# Sheet1_GMAX4651_MB.net
KiCad netlist of a schematic drawn in Altium Designer
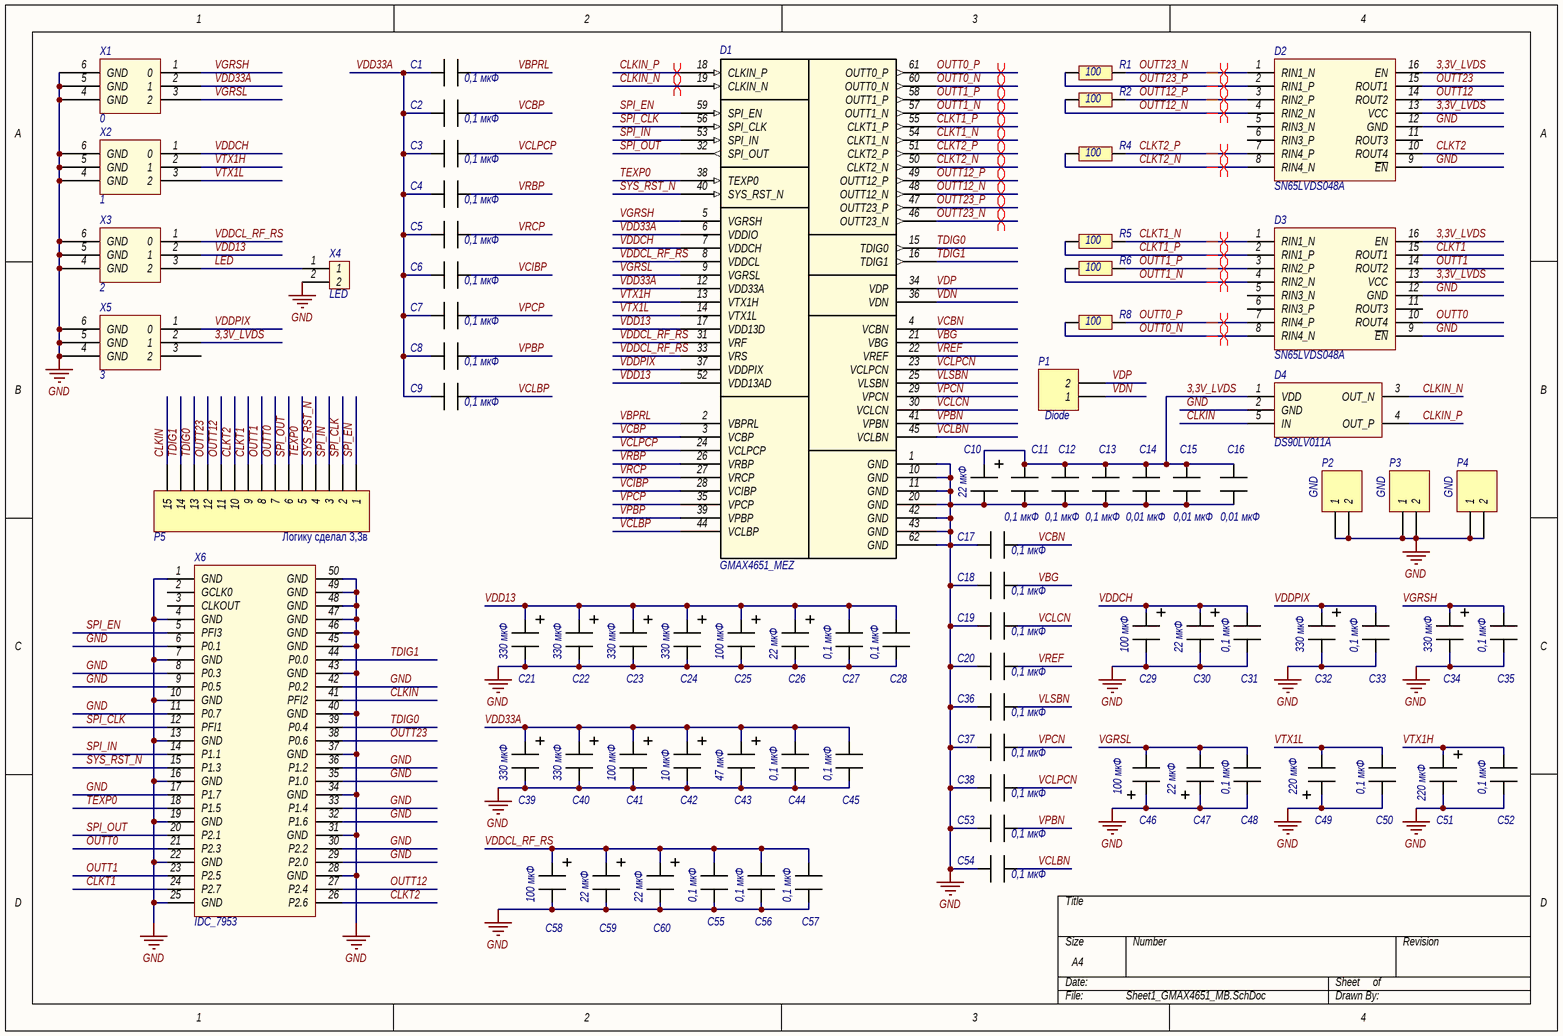
[diagram p0: Sheet1_GMAX4651_MB.SchDoc]

(export (version "E")
  (design (tool "Eeschema 10.0.6"))
  (components
    (comp (ref "C1") (value "0,1 мкФ") (footprint "CAP_SMALL") (libsource (lib "Schlib") (part "CAP_SMALL")))
    (comp (ref "C2") (value "0,1 мкФ") (footprint "CAP_SMALL") (libsource (lib "Schlib") (part "CAP_SMALL")))
    (comp (ref "C3") (value "0,1 мкФ") (footprint "CAP_SMALL") (libsource (lib "Schlib") (part "CAP_SMALL")))
    (comp (ref "C4") (value "0,1 мкФ") (footprint "CAP_SMALL") (libsource (lib "Schlib") (part "CAP_SMALL")))
    (comp (ref "C5") (value "0,1 мкФ") (footprint "CAP_SMALL") (libsource (lib "Schlib") (part "CAP_SMALL")))
    (comp (ref "C6") (value "0,1 мкФ") (footprint "CAP_SMALL") (libsource (lib "Schlib") (part "CAP_SMALL")))
    (comp (ref "C7") (value "0,1 мкФ") (footprint "CAP_SMALL") (libsource (lib "Schlib") (part "CAP_SMALL")))
    (comp (ref "C8") (value "0,1 мкФ") (footprint "CAP_SMALL") (libsource (lib "Schlib") (part "CAP_SMALL")))
    (comp (ref "C9") (value "0,1 мкФ") (footprint "CAP_SMALL") (libsource (lib "Schlib") (part "CAP_SMALL")))
    (comp (ref "C10")
      (value "22 мкФ")
      (footprint "Cap_0511_electrolitic")
      (libsource (lib "Schlib") (part "Cap_electrolotoc_0511"))
    )
    (comp (ref "C11") (value "0,1 мкФ") (footprint "CAP_SMALL") (libsource (lib "Schlib") (part "CAP_SMALL")))
    (comp (ref "C12") (value "0,1 мкФ") (footprint "CAP_SMALL") (libsource (lib "Schlib") (part "CAP_SMALL")))
    (comp (ref "C13") (value "0,1 мкФ") (footprint "CAP_SMALL") (libsource (lib "Schlib") (part "CAP_SMALL")))
    (comp (ref "C14")
      (value "0,01 мкФ")
      (footprint "CAP_SMALL")
      (libsource (lib "Schlib") (part "CAP_SMALL"))
    )
    (comp (ref "C15")
      (value "0,01 мкФ")
      (footprint "CAP_SMALL")
      (libsource (lib "Schlib") (part "CAP_SMALL"))
    )
    (comp (ref "C16")
      (value "0,01 мкФ")
      (footprint "CAP_SMALL")
      (libsource (lib "Schlib") (part "CAP_SMALL"))
    )
    (comp (ref "C17") (value "0,1 мкФ") (footprint "CAP_SMALL") (libsource (lib "Schlib") (part "CAP_SMALL")))
    (comp (ref "C18") (value "0,1 мкФ") (footprint "CAP_SMALL") (libsource (lib "Schlib") (part "CAP_SMALL")))
    (comp (ref "C19") (value "0,1 мкФ") (footprint "CAP_SMALL") (libsource (lib "Schlib") (part "CAP_SMALL")))
    (comp (ref "C20") (value "0,1 мкФ") (footprint "CAP_SMALL") (libsource (lib "Schlib") (part "CAP_SMALL")))
    (comp (ref "C21")
      (value "330 мкФ")
      (footprint "Cap_1013_electrolitic")
      (libsource (lib "Schlib") (part "Cap_electrolotoc_1013"))
    )
    (comp (ref "C22")
      (value "330 мкФ")
      (footprint "Cap_1013_electrolitic")
      (libsource (lib "Schlib") (part "Cap_electrolotoc_1013"))
    )
    (comp (ref "C23")
      (value "330 мкФ")
      (footprint "Cap_1013_electrolitic")
      (libsource (lib "Schlib") (part "Cap_electrolotoc_1013"))
    )
    (comp (ref "C24")
      (value "330 мкФ")
      (footprint "Cap_1013_electrolitic")
      (libsource (lib "Schlib") (part "Cap_electrolotoc_1013"))
    )
    (comp (ref "C25")
      (value "100 мкФ")
      (footprint "Cap_0612_electrolitic")
      (libsource (lib "Schlib") (part "Cap_electrolotoc_0612"))
    )
    (comp (ref "C26")
      (value "22 мкФ")
      (footprint "Cap_0511_electrolitic")
      (libsource (lib "Schlib") (part "Cap_electrolotoc_0511"))
    )
    (comp (ref "C27") (value "0,1 мкФ") (footprint "CAP_SMALL") (libsource (lib "Schlib") (part "CAP_SMALL")))
    (comp (ref "C28") (value "0,1 мкФ") (footprint "CAP_SMALL") (libsource (lib "Schlib") (part "CAP_SMALL")))
    (comp (ref "C29")
      (value "100 мкФ")
      (footprint "Cap_0612_electrolitic")
      (libsource (lib "Schlib") (part "Cap_electrolotoc_0612"))
    )
    (comp (ref "C30")
      (value "22 мкФ")
      (footprint "Cap_0511_electrolitic")
      (libsource (lib "Schlib") (part "Cap_electrolotoc_0511"))
    )
    (comp (ref "C31") (value "0,1 мкФ") (footprint "CAP_SMALL") (libsource (lib "Schlib") (part "CAP_SMALL")))
    (comp (ref "C32")
      (value "330 мкФ")
      (footprint "Cap_1013_electrolitic")
      (libsource (lib "Schlib") (part "Cap_electrolotoc_1013"))
    )
    (comp (ref "C33") (value "0,1 мкФ") (footprint "CAP_SMALL") (libsource (lib "Schlib") (part "CAP_SMALL")))
    (comp (ref "C34")
      (value "330 мкФ")
      (footprint "Cap_1013_electrolitic")
      (libsource (lib "Schlib") (part "Cap_electrolotoc_1013"))
    )
    (comp (ref "C35") (value "0,1 мкФ") (footprint "CAP_SMALL") (libsource (lib "Schlib") (part "CAP_SMALL")))
    (comp (ref "C36") (value "0,1 мкФ") (footprint "CAP_SMALL") (libsource (lib "Schlib") (part "CAP_SMALL")))
    (comp (ref "C37") (value "0,1 мкФ") (footprint "CAP_SMALL") (libsource (lib "Schlib") (part "CAP_SMALL")))
    (comp (ref "C38") (value "0,1 мкФ") (footprint "CAP_SMALL") (libsource (lib "Schlib") (part "CAP_SMALL")))
    (comp (ref "C39")
      (value "330 мкФ")
      (footprint "Cap_1013_electrolitic")
      (libsource (lib "Schlib") (part "Cap_electrolotoc_1013"))
    )
    (comp (ref "C40")
      (value "330 мкФ")
      (footprint "Cap_1013_electrolitic")
      (libsource (lib "Schlib") (part "Cap_electrolotoc_1013"))
    )
    (comp (ref "C41")
      (value "100 мкФ")
      (footprint "Cap_0612_electrolitic")
      (libsource (lib "Schlib") (part "Cap_electrolotoc_0612"))
    )
    (comp (ref "C42")
      (value "10 мкФ")
      (footprint "Cap_0511_electrolitic")
      (libsource (lib "Schlib") (part "Cap_electrolotoc_0511"))
    )
    (comp (ref "C43")
      (value "47 мкФ")
      (footprint "Cap_0612_electrolitic")
      (libsource (lib "Schlib") (part "Cap_electrolotoc_0612"))
    )
    (comp (ref "C44") (value "0,1 мкФ") (footprint "CAP_SMALL") (libsource (lib "Schlib") (part "CAP_SMALL")))
    (comp (ref "C45") (value "0,1 мкФ") (footprint "CAP_SMALL") (libsource (lib "Schlib") (part "CAP_SMALL")))
    (comp (ref "C46")
      (value "100 мкФ")
      (footprint "Cap_0612_electrolitic")
      (libsource (lib "Schlib") (part "Cap_electrolotoc_0612"))
    )
    (comp (ref "C47")
      (value "22 мкФ")
      (footprint "Cap_0511_electrolitic")
      (libsource (lib "Schlib") (part "Cap_electrolotoc_0511"))
    )
    (comp (ref "C48") (value "0,1 мкФ") (footprint "CAP_SMALL") (libsource (lib "Schlib") (part "CAP_SMALL")))
    (comp (ref "C49")
      (value "220 мкФ")
      (footprint "Cap_1013_electrolitic")
      (libsource (lib "Schlib") (part "Cap_electrolotoc_1013"))
    )
    (comp (ref "C50") (value "0,1 мкФ") (footprint "CAP_SMALL") (libsource (lib "Schlib") (part "CAP_SMALL")))
    (comp (ref "C51")
      (value "220 мкФ")
      (footprint "Cap_1013_electrolitic")
      (libsource (lib "Schlib") (part "Cap_electrolotoc_1013"))
    )
    (comp (ref "C52") (value "0,1 мкФ") (footprint "CAP_SMALL") (libsource (lib "Schlib") (part "CAP_SMALL")))
    (comp (ref "C53") (value "0,1 мкФ") (footprint "CAP_SMALL") (libsource (lib "Schlib") (part "CAP_SMALL")))
    (comp (ref "C54") (value "0,1 мкФ") (footprint "CAP_SMALL") (libsource (lib "Schlib") (part "CAP_SMALL")))
    (comp (ref "C55") (value "0,1 мкФ") (footprint "CAP_SMALL") (libsource (lib "Schlib") (part "CAP_SMALL")))
    (comp (ref "C56") (value "0,1 мкФ") (footprint "CAP_SMALL") (libsource (lib "Schlib") (part "CAP_SMALL")))
    (comp (ref "C57") (value "0,1 мкФ") (footprint "CAP_SMALL") (libsource (lib "Schlib") (part "CAP_SMALL")))
    (comp (ref "C58")
      (value "100 мкФ")
      (footprint "Cap_0612_electrolitic")
      (libsource (lib "Schlib") (part "Cap_electrolotoc_0612"))
    )
    (comp (ref "C59")
      (value "22 мкФ")
      (footprint "Cap_0511_electrolitic")
      (libsource (lib "Schlib") (part "Cap_electrolotoc_0511"))
    )
    (comp (ref "C60")
      (value "22 мкФ")
      (footprint "Cap_0511_electrolitic")
      (libsource (lib "Schlib") (part "Cap_electrolotoc_0511"))
    )
    (comp (ref "D1")
      (value "GMAX4651_MEZ")
      (footprint "GMAX4651_MEZ")
      (libsource (lib "Schlib") (part "GMAX4651_MEZ"))
    )
    (comp (ref "D2")
      (value "SN65LVDS048A")
      (footprint "SN65LVDS048A (4LVDS)")
      (libsource (lib "Schlib") (part "SN65LVDS048A (4LVDS)"))
    )
    (comp (ref "D3")
      (value "SN65LVDS048A")
      (footprint "SN65LVDS048A (4LVDS)")
      (libsource (lib "Schlib") (part "SN65LVDS048A (4LVDS)"))
    )
    (comp (ref "D4")
      (value "DS90LV011A")
      (footprint "DS90LV011A")
      (description "LVDS Driver 1 ch")
      (libsource (lib "Schlib") (part "DS90LV011A"))
    )
    (comp (ref "P1")
      (value "Diode")
      (footprint "HDR1X2")
      (description "Header, 2-Pin")
      (fields (field (name "PUBLISHER") "Altium Limited"))
      (libsource (lib "Miscellaneous Connectors") (part "Header 2"))
    )
    (comp (ref "P2")
      (value "GND")
      (footprint "HDR1X2")
      (description "Header, 2-Pin")
      (fields (field (name "PUBLISHER") "Altium Limited"))
      (libsource (lib "") (part "Header 2_1"))
    )
    (comp (ref "P3")
      (value "GND")
      (footprint "HDR1X2")
      (description "Header, 2-Pin")
      (fields (field (name "PUBLISHER") "Altium Limited"))
      (libsource (lib "") (part "Header 2_1"))
    )
    (comp (ref "P4")
      (value "GND")
      (footprint "HDR1X2")
      (description "Header, 2-Pin")
      (fields (field (name "PUBLISHER") "Altium Limited"))
      (libsource (lib "") (part "Header 2_1"))
    )
    (comp (ref "P5")
      (value "Header 15")
      (footprint "HDR1X15")
      (description "Header, 15-Pin")
      (fields (field (name "PUBLISHER") "Altium Limited"))
      (libsource (lib "Miscellaneous Connectors") (part "Header 15"))
    )
    (comp (ref "R1") (value "100") (footprint "RES") (libsource (lib "Schlib") (part "RES")))
    (comp (ref "R2") (value "100") (footprint "RES") (libsource (lib "Schlib") (part "RES")))
    (comp (ref "R4") (value "100") (footprint "RES") (libsource (lib "Schlib") (part "RES")))
    (comp (ref "R5") (value "100") (footprint "RES") (libsource (lib "Schlib") (part "RES")))
    (comp (ref "R6") (value "100") (footprint "RES") (libsource (lib "Schlib") (part "RES")))
    (comp (ref "R8") (value "100") (footprint "RES") (libsource (lib "Schlib") (part "RES")))
    (comp (ref "X1") (value "0") (footprint "POWER") (libsource (lib "Schlib") (part "POWER")))
    (comp (ref "X2") (value "1") (footprint "POWER") (libsource (lib "Schlib") (part "POWER")))
    (comp (ref "X3") (value "2") (footprint "POWER") (libsource (lib "Schlib") (part "POWER")))
    (comp (ref "X4") (value "LED") (footprint "KLEMMNIK_2") (libsource (lib "Schlib") (part "KLEMMNIK_2")))
    (comp (ref "X5") (value "3") (footprint "POWER") (libsource (lib "Schlib") (part "POWER")))
    (comp (ref "X6") (value "IDC_7953") (footprint "IDC_7953") (libsource (lib "VPL") (part "IDC_7953")))
  )
  (nets
    (net (code "1") (name "/3,3V_LVDS") (class "Default")
      (node (ref "C10") (pin "1") (pinfunction "1_1") (pintype "passive"))
      (node (ref "C11") (pin "2") (pinfunction "2_2") (pintype "passive"))
      (node (ref "C12") (pin "2") (pinfunction "2_2") (pintype "passive"))
      (node (ref "C13") (pin "2") (pinfunction "2_2") (pintype "passive"))
      (node (ref "C14") (pin "2") (pinfunction "2_2") (pintype "passive"))
      (node (ref "C15") (pin "2") (pinfunction "2_2") (pintype "passive"))
      (node (ref "C16") (pin "2") (pinfunction "2_2") (pintype "passive"))
      (node (ref "D2") (pin "13") (pinfunction "VCC_13") (pintype "passive"))
      (node (ref "D2") (pin "16") (pinfunction "EN_16") (pintype "passive"))
      (node (ref "D3") (pin "13") (pinfunction "VCC_13") (pintype "passive"))
      (node (ref "D3") (pin "16") (pinfunction "EN_16") (pintype "passive"))
      (node (ref "D4") (pin "1") (pinfunction "VDD_1") (pintype "passive"))
      (node (ref "X5") (pin "2") (pinfunction "1_2") (pintype "passive"))
    )
    (net (code "2") (name "/CLKIN") (class "Default")
      (node (ref "D4") (pin "5") (pinfunction "IN_5") (pintype "passive"))
      (node (ref "P5") (pin "15") (pinfunction "15_15") (pintype "passive"))
      (node (ref "X6") (pin "41") (pinfunction "PFI2_41") (pintype "passive"))
    )
    (net (code "3") (name "/CLKIN_N") (class "Default")
      (node (ref "D1") (pin "19") (pinfunction "CLKIN_N_19") (pintype "input"))
      (node (ref "D4") (pin "3") (pinfunction "OUT_N_3") (pintype "passive"))
    )
    (net (code "4") (name "/CLKIN_P") (class "Default")
      (node (ref "D1") (pin "18") (pinfunction "CLKIN_P_18") (pintype "input"))
      (node (ref "D4") (pin "4") (pinfunction "OUT_P_4") (pintype "passive"))
    )
    (net (code "5") (name "/CLKT1") (class "Default")
      (node (ref "D3") (pin "15") (pinfunction "ROUT1_15") (pintype "passive"))
      (node (ref "P5") (pin "9") (pinfunction "9_9") (pintype "passive"))
      (node (ref "X6") (pin "24") (pinfunction "P2.7_24") (pintype "passive"))
    )
    (net (code "6") (name "/CLKT1_N") (class "Default")
      (node (ref "D1") (pin "54") (pinfunction "CLKT1_N_54") (pintype "output"))
      (node (ref "D3") (pin "1") (pinfunction "RIN1_N_1") (pintype "passive"))
      (node (ref "R5") (pin "1") (pinfunction "1_1") (pintype "passive"))
    )
    (net (code "7") (name "/CLKT1_P") (class "Default")
      (node (ref "D1") (pin "55") (pinfunction "CLKT1_P_55") (pintype "output"))
      (node (ref "D3") (pin "2") (pinfunction "RIN1_P_2") (pintype "passive"))
      (node (ref "R5") (pin "2") (pinfunction "2_2") (pintype "passive"))
    )
    (net (code "8") (name "/CLKT2") (class "Default")
      (node (ref "D2") (pin "10") (pinfunction "ROUT4_10") (pintype "passive"))
      (node (ref "P5") (pin "10") (pinfunction "10_10") (pintype "passive"))
      (node (ref "X6") (pin "26") (pinfunction "P2.6_26") (pintype "passive"))
    )
    (net (code "9") (name "/CLKT2_N") (class "Default")
      (node (ref "D1") (pin "50") (pinfunction "CLKT2_N_50") (pintype "output"))
      (node (ref "D2") (pin "8") (pinfunction "RIN4_N_8") (pintype "passive"))
      (node (ref "R4") (pin "2") (pinfunction "2_2") (pintype "passive"))
    )
    (net (code "10") (name "/CLKT2_P") (class "Default")
      (node (ref "D1") (pin "51") (pinfunction "CLKT2_P_51") (pintype "output"))
      (node (ref "D2") (pin "7") (pinfunction "RIN4_P_7") (pintype "passive"))
      (node (ref "R4") (pin "1") (pinfunction "1_1") (pintype "passive"))
    )
    (net (code "11") (name "/LED") (class "Default")
      (node (ref "X3") (pin "3") (pinfunction "2_3") (pintype "passive"))
      (node (ref "X4") (pin "1") (pinfunction "1_1") (pintype "passive"))
    )
    (net (code "12") (name "/OUTT0") (class "Default")
      (node (ref "D3") (pin "10") (pinfunction "ROUT4_10") (pintype "passive"))
      (node (ref "P5") (pin "7") (pinfunction "7_7") (pintype "passive"))
      (node (ref "X6") (pin "21") (pinfunction "P2.3_21") (pintype "passive"))
    )
    (net (code "13") (name "/OUTT0_N") (class "Default")
      (node (ref "D1") (pin "60") (pinfunction "OUTT0_N_60") (pintype "output"))
      (node (ref "D3") (pin "8") (pinfunction "RIN4_N_8") (pintype "passive"))
      (node (ref "R8") (pin "2") (pinfunction "2_2") (pintype "passive"))
    )
    (net (code "14") (name "/OUTT0_P") (class "Default")
      (node (ref "D1") (pin "61") (pinfunction "OUTT0_P_61") (pintype "output"))
      (node (ref "D3") (pin "7") (pinfunction "RIN4_P_7") (pintype "passive"))
      (node (ref "R8") (pin "1") (pinfunction "1_1") (pintype "passive"))
    )
    (net (code "15") (name "/OUTT1") (class "Default")
      (node (ref "D3") (pin "14") (pinfunction "ROUT2_14") (pintype "passive"))
      (node (ref "P5") (pin "8") (pinfunction "8_8") (pintype "passive"))
      (node (ref "X6") (pin "23") (pinfunction "P2.5_23") (pintype "passive"))
    )
    (net (code "16") (name "/OUTT1_N") (class "Default")
      (node (ref "D1") (pin "57") (pinfunction "OUTT1_N_57") (pintype "output"))
      (node (ref "D3") (pin "4") (pinfunction "RIN2_N_4") (pintype "passive"))
      (node (ref "R6") (pin "2") (pinfunction "2_2") (pintype "passive"))
    )
    (net (code "17") (name "/OUTT1_P") (class "Default")
      (node (ref "D1") (pin "58") (pinfunction "OUTT1_P_58") (pintype "output"))
      (node (ref "D3") (pin "3") (pinfunction "RIN2_P_3") (pintype "passive"))
      (node (ref "R6") (pin "1") (pinfunction "1_1") (pintype "passive"))
    )
    (net (code "18") (name "/OUTT12") (class "Default")
      (node (ref "D2") (pin "14") (pinfunction "ROUT2_14") (pintype "passive"))
      (node (ref "P5") (pin "11") (pinfunction "11_11") (pintype "passive"))
      (node (ref "X6") (pin "27") (pinfunction "P2.4_27") (pintype "passive"))
    )
    (net (code "19") (name "/OUTT12_N") (class "Default")
      (node (ref "D1") (pin "48") (pinfunction "OUTT12_N_48") (pintype "output"))
      (node (ref "D2") (pin "4") (pinfunction "RIN2_N_4") (pintype "passive"))
      (node (ref "R2") (pin "2") (pinfunction "2_2") (pintype "passive"))
    )
    (net (code "20") (name "/OUTT12_P") (class "Default")
      (node (ref "D1") (pin "49") (pinfunction "OUTT12_P_49") (pintype "output"))
      (node (ref "D2") (pin "3") (pinfunction "RIN2_P_3") (pintype "passive"))
      (node (ref "R2") (pin "1") (pinfunction "1_1") (pintype "passive"))
    )
    (net (code "21") (name "/OUTT23") (class "Default")
      (node (ref "D2") (pin "15") (pinfunction "ROUT1_15") (pintype "passive"))
      (node (ref "P5") (pin "12") (pinfunction "12_12") (pintype "passive"))
      (node (ref "X6") (pin "38") (pinfunction "P0.6_38") (pintype "passive"))
    )
    (net (code "22") (name "/OUTT23_N") (class "Default")
      (node (ref "D1") (pin "46") (pinfunction "OUTT23_N_46") (pintype "output"))
      (node (ref "D2") (pin "1") (pinfunction "RIN1_N_1") (pintype "passive"))
      (node (ref "R1") (pin "1") (pinfunction "1_1") (pintype "passive"))
    )
    (net (code "23") (name "/OUTT23_P") (class "Default")
      (node (ref "D1") (pin "47") (pinfunction "OUTT23_P_47") (pintype "output"))
      (node (ref "D2") (pin "2") (pinfunction "RIN1_P_2") (pintype "passive"))
      (node (ref "R1") (pin "2") (pinfunction "2_2") (pintype "passive"))
    )
    (net (code "24") (name "/SPI_CLK") (class "Default")
      (node (ref "D1") (pin "56") (pinfunction "SPI_CLK_56") (pintype "input"))
      (node (ref "P5") (pin "2") (pinfunction "2_2") (pintype "passive"))
      (node (ref "X6") (pin "12") (pinfunction "PFI1_12") (pintype "passive"))
    )
    (net (code "25") (name "/SPI_EN") (class "Default")
      (node (ref "D1") (pin "59") (pinfunction "SPI_EN_59") (pintype "input"))
      (node (ref "P5") (pin "1") (pinfunction "1_1") (pintype "passive"))
      (node (ref "X6") (pin "5") (pinfunction "PFI3_5") (pintype "passive"))
    )
    (net (code "26") (name "/SPI_IN") (class "Default")
      (node (ref "D1") (pin "53") (pinfunction "SPI_IN_53") (pintype "input"))
      (node (ref "P5") (pin "3") (pinfunction "3_3") (pintype "passive"))
      (node (ref "X6") (pin "14") (pinfunction "P1.1_14") (pintype "passive"))
    )
    (net (code "27") (name "/SPI_OUT") (class "Default")
      (node (ref "D1") (pin "32") (pinfunction "SPI_OUT_32") (pintype "output"))
      (node (ref "P5") (pin "6") (pinfunction "6_6") (pintype "passive"))
      (node (ref "X6") (pin "20") (pinfunction "P2.1_20") (pintype "passive"))
    )
    (net (code "28") (name "/SYS_RST_N") (class "Default")
      (node (ref "D1") (pin "40") (pinfunction "SYS_RST_N_40") (pintype "input"))
      (node (ref "P5") (pin "4") (pinfunction "4_4") (pintype "passive"))
      (node (ref "X6") (pin "15") (pinfunction "P1.3_15") (pintype "passive"))
    )
    (net (code "29") (name "/TDIG0") (class "Default")
      (node (ref "D1") (pin "15") (pinfunction "TDIG0_15") (pintype "output"))
      (node (ref "P5") (pin "13") (pinfunction "13_13") (pintype "passive"))
      (node (ref "X6") (pin "39") (pinfunction "P0.4_39") (pintype "passive"))
    )
    (net (code "30") (name "/TDIG1") (class "Default")
      (node (ref "D1") (pin "16") (pinfunction "TDIG1_16") (pintype "output"))
      (node (ref "P5") (pin "14") (pinfunction "14_14") (pintype "passive"))
      (node (ref "X6") (pin "44") (pinfunction "P0.0_44") (pintype "passive"))
    )
    (net (code "31") (name "/TEXP0") (class "Default")
      (node (ref "D1") (pin "38") (pinfunction "TEXP0_38") (pintype "input"))
      (node (ref "P5") (pin "5") (pinfunction "5_5") (pintype "passive"))
      (node (ref "X6") (pin "18") (pinfunction "P1.5_18") (pintype "passive"))
    )
    (net (code "32") (name "/VBG") (class "Default")
      (node (ref "C18") (pin "1") (pinfunction "1_1") (pintype "passive"))
      (node (ref "D1") (pin "21") (pinfunction "VBG_21") (pintype "passive"))
    )
    (net (code "33") (name "/VBPRL") (class "Default")
      (node (ref "C1") (pin "1") (pinfunction "1_1") (pintype "passive"))
      (node (ref "D1") (pin "2") (pinfunction "VBPRL_2") (pintype "passive"))
    )
    (net (code "34") (name "/VCBN") (class "Default")
      (node (ref "C17") (pin "1") (pinfunction "1_1") (pintype "passive"))
      (node (ref "D1") (pin "4") (pinfunction "VCBN_4") (pintype "passive"))
    )
    (net (code "35") (name "/VCBP") (class "Default")
      (node (ref "C2") (pin "1") (pinfunction "1_1") (pintype "passive"))
      (node (ref "D1") (pin "3") (pinfunction "VCBP_3") (pintype "passive"))
    )
    (net (code "36") (name "/VCIBP") (class "Default")
      (node (ref "C6") (pin "1") (pinfunction "1_1") (pintype "passive"))
      (node (ref "D1") (pin "28") (pinfunction "VCIBP_28") (pintype "passive"))
    )
    (net (code "37") (name "/VCLBN") (class "Default")
      (node (ref "C54") (pin "1") (pinfunction "1_1") (pintype "passive"))
      (node (ref "D1") (pin "45") (pinfunction "VCLBN_45") (pintype "passive"))
    )
    (net (code "38") (name "/VCLBP") (class "Default")
      (node (ref "C9") (pin "1") (pinfunction "1_1") (pintype "passive"))
      (node (ref "D1") (pin "44") (pinfunction "VCLBP_44") (pintype "passive"))
    )
    (net (code "39") (name "/VCLCN") (class "Default")
      (node (ref "C19") (pin "1") (pinfunction "1_1") (pintype "passive"))
      (node (ref "D1") (pin "30") (pinfunction "VCLCN_30") (pintype "passive"))
    )
    (net (code "40") (name "/VCLPCN") (class "Default")
      (node (ref "C38") (pin "1") (pinfunction "1_1") (pintype "passive"))
      (node (ref "D1") (pin "23") (pinfunction "VCLPCN_23") (pintype "passive"))
    )
    (net (code "41") (name "/VCLPCP") (class "Default")
      (node (ref "C3") (pin "1") (pinfunction "1_1") (pintype "passive"))
      (node (ref "D1") (pin "24") (pinfunction "VCLPCP_24") (pintype "passive"))
    )
    (net (code "42") (name "/VDD13") (class "Default")
      (node (ref "C21") (pin "1") (pinfunction "1_1") (pintype "passive"))
      (node (ref "C22") (pin "1") (pinfunction "1_1") (pintype "passive"))
      (node (ref "C23") (pin "1") (pinfunction "1_1") (pintype "passive"))
      (node (ref "C24") (pin "1") (pinfunction "1_1") (pintype "passive"))
      (node (ref "C25") (pin "1") (pinfunction "1_1") (pintype "passive"))
      (node (ref "C26") (pin "1") (pinfunction "1_1") (pintype "passive"))
      (node (ref "C27") (pin "1") (pinfunction "1_1") (pintype "passive"))
      (node (ref "C28") (pin "1") (pinfunction "1_1") (pintype "passive"))
      (node (ref "D1") (pin "17") (pinfunction "VDD13D_17") (pintype "passive"))
      (node (ref "D1") (pin "52") (pinfunction "VDD13AD_52") (pintype "passive"))
      (node (ref "X3") (pin "2") (pinfunction "1_2") (pintype "passive"))
    )
    (net (code "43") (name "/VDD33A") (class "Default")
      (node (ref "C1") (pin "2") (pinfunction "2_2") (pintype "passive"))
      (node (ref "C2") (pin "2") (pinfunction "2_2") (pintype "passive"))
      (node (ref "C3") (pin "2") (pinfunction "2_2") (pintype "passive"))
      (node (ref "C39") (pin "1") (pinfunction "1_1") (pintype "passive"))
      (node (ref "C4") (pin "2") (pinfunction "2_2") (pintype "passive"))
      (node (ref "C40") (pin "1") (pinfunction "1_1") (pintype "passive"))
      (node (ref "C41") (pin "1") (pinfunction "1_1") (pintype "passive"))
      (node (ref "C42") (pin "1") (pinfunction "1_1") (pintype "passive"))
      (node (ref "C43") (pin "1") (pinfunction "1_1") (pintype "passive"))
      (node (ref "C44") (pin "1") (pinfunction "1_1") (pintype "passive"))
      (node (ref "C45") (pin "1") (pinfunction "1_1") (pintype "passive"))
      (node (ref "C5") (pin "2") (pinfunction "2_2") (pintype "passive"))
      (node (ref "C6") (pin "2") (pinfunction "2_2") (pintype "passive"))
      (node (ref "C7") (pin "2") (pinfunction "2_2") (pintype "passive"))
      (node (ref "C8") (pin "2") (pinfunction "2_2") (pintype "passive"))
      (node (ref "C9") (pin "2") (pinfunction "2_2") (pintype "passive"))
      (node (ref "D1") (pin "12") (pinfunction "VDD33A_12") (pintype "passive"))
      (node (ref "D1") (pin "6") (pinfunction "VDDIO_6") (pintype "passive"))
      (node (ref "X1") (pin "2") (pinfunction "1_2") (pintype "passive"))
    )
    (net (code "44") (name "/VDDCH") (class "Default")
      (node (ref "C29") (pin "1") (pinfunction "1_1") (pintype "passive"))
      (node (ref "C30") (pin "1") (pinfunction "1_1") (pintype "passive"))
      (node (ref "C31") (pin "1") (pinfunction "1_1") (pintype "passive"))
      (node (ref "D1") (pin "7") (pinfunction "VDDCH_7") (pintype "passive"))
      (node (ref "X2") (pin "1") (pinfunction "0_1") (pintype "passive"))
    )
    (net (code "45") (name "/VDDCL_RF_RS") (class "Default")
      (node (ref "C55") (pin "1") (pinfunction "1_1") (pintype "passive"))
      (node (ref "C56") (pin "1") (pinfunction "1_1") (pintype "passive"))
      (node (ref "C57") (pin "1") (pinfunction "1_1") (pintype "passive"))
      (node (ref "C58") (pin "1") (pinfunction "1_1") (pintype "passive"))
      (node (ref "C59") (pin "1") (pinfunction "1_1") (pintype "passive"))
      (node (ref "C60") (pin "1") (pinfunction "1_1") (pintype "passive"))
      (node (ref "D1") (pin "31") (pinfunction "VRF_31") (pintype "passive"))
      (node (ref "D1") (pin "33") (pinfunction "VRS_33") (pintype "passive"))
      (node (ref "D1") (pin "8") (pinfunction "VDDCL_8") (pintype "passive"))
      (node (ref "X3") (pin "1") (pinfunction "0_1") (pintype "passive"))
    )
    (net (code "46") (name "/VDDPIX") (class "Default")
      (node (ref "C32") (pin "1") (pinfunction "1_1") (pintype "passive"))
      (node (ref "C33") (pin "1") (pinfunction "1_1") (pintype "passive"))
      (node (ref "D1") (pin "37") (pinfunction "VDDPIX_37") (pintype "passive"))
      (node (ref "X5") (pin "1") (pinfunction "0_1") (pintype "passive"))
    )
    (net (code "47") (name "/VDN") (class "Default")
      (node (ref "D1") (pin "36") (pinfunction "VDN_36") (pintype "passive"))
      (node (ref "P1") (pin "1") (pinfunction "1_1") (pintype "passive"))
    )
    (net (code "48") (name "/VDP") (class "Default")
      (node (ref "D1") (pin "34") (pinfunction "VDP_34") (pintype "passive"))
      (node (ref "P1") (pin "2") (pinfunction "2_2") (pintype "passive"))
    )
    (net (code "49") (name "/VGRSH") (class "Default")
      (node (ref "C34") (pin "1") (pinfunction "1_1") (pintype "passive"))
      (node (ref "C35") (pin "1") (pinfunction "1_1") (pintype "passive"))
      (node (ref "D1") (pin "5") (pinfunction "VGRSH_5") (pintype "passive"))
      (node (ref "X1") (pin "1") (pinfunction "0_1") (pintype "passive"))
    )
    (net (code "50") (name "/VGRSL") (class "Default")
      (node (ref "C46") (pin "2") (pinfunction "2_2") (pintype "passive"))
      (node (ref "C47") (pin "2") (pinfunction "2_2") (pintype "passive"))
      (node (ref "C48") (pin "1") (pinfunction "1_1") (pintype "passive"))
      (node (ref "D1") (pin "9") (pinfunction "VGRSL_9") (pintype "passive"))
      (node (ref "X1") (pin "3") (pinfunction "2_3") (pintype "passive"))
    )
    (net (code "51") (name "/VLSBN") (class "Default")
      (node (ref "C36") (pin "1") (pinfunction "1_1") (pintype "passive"))
      (node (ref "D1") (pin "25") (pinfunction "VLSBN_25") (pintype "passive"))
    )
    (net (code "52") (name "/VPBN") (class "Default")
      (node (ref "C53") (pin "1") (pinfunction "1_1") (pintype "passive"))
      (node (ref "D1") (pin "41") (pinfunction "VPBN_41") (pintype "passive"))
    )
    (net (code "53") (name "/VPBP") (class "Default")
      (node (ref "C8") (pin "1") (pinfunction "1_1") (pintype "passive"))
      (node (ref "D1") (pin "39") (pinfunction "VPBP_39") (pintype "passive"))
    )
    (net (code "54") (name "/VPCN") (class "Default")
      (node (ref "C37") (pin "1") (pinfunction "1_1") (pintype "passive"))
      (node (ref "D1") (pin "29") (pinfunction "VPCN_29") (pintype "passive"))
    )
    (net (code "55") (name "/VPCP") (class "Default")
      (node (ref "C7") (pin "1") (pinfunction "1_1") (pintype "passive"))
      (node (ref "D1") (pin "35") (pinfunction "VPCP_35") (pintype "passive"))
    )
    (net (code "56") (name "/VRBP") (class "Default")
      (node (ref "C4") (pin "1") (pinfunction "1_1") (pintype "passive"))
      (node (ref "D1") (pin "26") (pinfunction "VRBP_26") (pintype "passive"))
    )
    (net (code "57") (name "/VRCP") (class "Default")
      (node (ref "C5") (pin "1") (pinfunction "1_1") (pintype "passive"))
      (node (ref "D1") (pin "27") (pinfunction "VRCP_27") (pintype "passive"))
    )
    (net (code "58") (name "/VREF") (class "Default")
      (node (ref "C20") (pin "1") (pinfunction "1_1") (pintype "passive"))
      (node (ref "D1") (pin "22") (pinfunction "VREF_22") (pintype "passive"))
    )
    (net (code "59") (name "/VTX1H") (class "Default")
      (node (ref "C51") (pin "1") (pinfunction "1_1") (pintype "passive"))
      (node (ref "C52") (pin "1") (pinfunction "1_1") (pintype "passive"))
      (node (ref "D1") (pin "13") (pinfunction "VTX1H_13") (pintype "passive"))
      (node (ref "X2") (pin "2") (pinfunction "1_2") (pintype "passive"))
    )
    (net (code "60") (name "/VTX1L") (class "Default")
      (node (ref "C49") (pin "2") (pinfunction "2_2") (pintype "passive"))
      (node (ref "C50") (pin "1") (pinfunction "1_1") (pintype "passive"))
      (node (ref "D1") (pin "14") (pinfunction "VTX1L_14") (pintype "passive"))
      (node (ref "X2") (pin "3") (pinfunction "2_3") (pintype "passive"))
    )
    (net (code "61") (name "GND") (class "Default")
      (node (ref "C10") (pin "2") (pinfunction "2_2") (pintype "passive"))
      (node (ref "C11") (pin "1") (pinfunction "1_1") (pintype "passive"))
      (node (ref "C12") (pin "1") (pinfunction "1_1") (pintype "passive"))
      (node (ref "C13") (pin "1") (pinfunction "1_1") (pintype "passive"))
      (node (ref "C14") (pin "1") (pinfunction "1_1") (pintype "passive"))
      (node (ref "C15") (pin "1") (pinfunction "1_1") (pintype "passive"))
      (node (ref "C16") (pin "1") (pinfunction "1_1") (pintype "passive"))
      (node (ref "C17") (pin "2") (pinfunction "2_2") (pintype "passive"))
      (node (ref "C18") (pin "2") (pinfunction "2_2") (pintype "passive"))
      (node (ref "C19") (pin "2") (pinfunction "2_2") (pintype "passive"))
      (node (ref "C20") (pin "2") (pinfunction "2_2") (pintype "passive"))
      (node (ref "C21") (pin "2") (pinfunction "2_2") (pintype "passive"))
      (node (ref "C22") (pin "2") (pinfunction "2_2") (pintype "passive"))
      (node (ref "C23") (pin "2") (pinfunction "2_2") (pintype "passive"))
      (node (ref "C24") (pin "2") (pinfunction "2_2") (pintype "passive"))
      (node (ref "C25") (pin "2") (pinfunction "2_2") (pintype "passive"))
      (node (ref "C26") (pin "2") (pinfunction "2_2") (pintype "passive"))
      (node (ref "C27") (pin "2") (pinfunction "2_2") (pintype "passive"))
      (node (ref "C28") (pin "2") (pinfunction "2_2") (pintype "passive"))
      (node (ref "C29") (pin "2") (pinfunction "2_2") (pintype "passive"))
      (node (ref "C30") (pin "2") (pinfunction "2_2") (pintype "passive"))
      (node (ref "C31") (pin "2") (pinfunction "2_2") (pintype "passive"))
      (node (ref "C32") (pin "2") (pinfunction "2_2") (pintype "passive"))
      (node (ref "C33") (pin "2") (pinfunction "2_2") (pintype "passive"))
      (node (ref "C34") (pin "2") (pinfunction "2_2") (pintype "passive"))
      (node (ref "C35") (pin "2") (pinfunction "2_2") (pintype "passive"))
      (node (ref "C36") (pin "2") (pinfunction "2_2") (pintype "passive"))
      (node (ref "C37") (pin "2") (pinfunction "2_2") (pintype "passive"))
      (node (ref "C38") (pin "2") (pinfunction "2_2") (pintype "passive"))
      (node (ref "C39") (pin "2") (pinfunction "2_2") (pintype "passive"))
      (node (ref "C40") (pin "2") (pinfunction "2_2") (pintype "passive"))
      (node (ref "C41") (pin "2") (pinfunction "2_2") (pintype "passive"))
      (node (ref "C42") (pin "2") (pinfunction "2_2") (pintype "passive"))
      (node (ref "C43") (pin "2") (pinfunction "2_2") (pintype "passive"))
      (node (ref "C44") (pin "2") (pinfunction "2_2") (pintype "passive"))
      (node (ref "C45") (pin "2") (pinfunction "2_2") (pintype "passive"))
      (node (ref "C46") (pin "1") (pinfunction "1_1") (pintype "passive"))
      (node (ref "C47") (pin "1") (pinfunction "1_1") (pintype "passive"))
      (node (ref "C48") (pin "2") (pinfunction "2_2") (pintype "passive"))
      (node (ref "C49") (pin "1") (pinfunction "1_1") (pintype "passive"))
      (node (ref "C50") (pin "2") (pinfunction "2_2") (pintype "passive"))
      (node (ref "C51") (pin "2") (pinfunction "2_2") (pintype "passive"))
      (node (ref "C52") (pin "2") (pinfunction "2_2") (pintype "passive"))
      (node (ref "C53") (pin "2") (pinfunction "2_2") (pintype "passive"))
      (node (ref "C54") (pin "2") (pinfunction "2_2") (pintype "passive"))
      (node (ref "C55") (pin "2") (pinfunction "2_2") (pintype "passive"))
      (node (ref "C56") (pin "2") (pinfunction "2_2") (pintype "passive"))
      (node (ref "C57") (pin "2") (pinfunction "2_2") (pintype "passive"))
      (node (ref "C58") (pin "2") (pinfunction "2_2") (pintype "passive"))
      (node (ref "C59") (pin "2") (pinfunction "2_2") (pintype "passive"))
      (node (ref "C60") (pin "2") (pinfunction "2_2") (pintype "passive"))
      (node (ref "D1") (pin "1") (pinfunction "GND_1") (pintype "passive"))
      (node (ref "D1") (pin "10") (pinfunction "GND_10") (pintype "passive"))
      (node (ref "D1") (pin "11") (pinfunction "GND_11") (pintype "passive"))
      (node (ref "D1") (pin "20") (pinfunction "GND_20") (pintype "passive"))
      (node (ref "D1") (pin "42") (pinfunction "GND_42") (pintype "passive"))
      (node (ref "D1") (pin "43") (pinfunction "GND_43") (pintype "passive"))
      (node (ref "D1") (pin "62") (pinfunction "GND_62") (pintype "passive"))
      (node (ref "D2") (pin "12") (pinfunction "GND_12") (pintype "passive"))
      (node (ref "D2") (pin "9") (pinfunction "~{EN}_9") (pintype "passive"))
      (node (ref "D3") (pin "12") (pinfunction "GND_12") (pintype "passive"))
      (node (ref "D3") (pin "9") (pinfunction "~{EN}_9") (pintype "passive"))
      (node (ref "D4") (pin "2") (pinfunction "GND_2") (pintype "passive"))
      (node (ref "P2") (pin "1") (pinfunction "1_1") (pintype "passive"))
      (node (ref "P2") (pin "2") (pinfunction "2_2") (pintype "passive"))
      (node (ref "P3") (pin "1") (pinfunction "1_1") (pintype "passive"))
      (node (ref "P3") (pin "2") (pinfunction "2_2") (pintype "passive"))
      (node (ref "P4") (pin "1") (pinfunction "1_1") (pintype "passive"))
      (node (ref "P4") (pin "2") (pinfunction "2_2") (pintype "passive"))
      (node (ref "X1") (pin "4") (pinfunction "GND_4") (pintype "passive"))
      (node (ref "X1") (pin "5") (pinfunction "GND_5") (pintype "passive"))
      (node (ref "X1") (pin "6") (pinfunction "GND_6") (pintype "passive"))
      (node (ref "X2") (pin "4") (pinfunction "GND_4") (pintype "passive"))
      (node (ref "X2") (pin "5") (pinfunction "GND_5") (pintype "passive"))
      (node (ref "X2") (pin "6") (pinfunction "GND_6") (pintype "passive"))
      (node (ref "X3") (pin "4") (pinfunction "GND_4") (pintype "passive"))
      (node (ref "X3") (pin "5") (pinfunction "GND_5") (pintype "passive"))
      (node (ref "X3") (pin "6") (pinfunction "GND_6") (pintype "passive"))
      (node (ref "X4") (pin "2") (pinfunction "2_2") (pintype "passive"))
      (node (ref "X5") (pin "4") (pinfunction "GND_4") (pintype "passive"))
      (node (ref "X5") (pin "5") (pinfunction "GND_5") (pintype "passive"))
      (node (ref "X5") (pin "6") (pinfunction "GND_6") (pintype "passive"))
      (node (ref "X6") (pin "1") (pinfunction "GND_1") (pintype "passive"))
      (node (ref "X6") (pin "10") (pinfunction "GND_10") (pintype "passive"))
      (node (ref "X6") (pin "11") (pinfunction "P0.7_11") (pintype "passive"))
      (node (ref "X6") (pin "13") (pinfunction "GND_13") (pintype "passive"))
      (node (ref "X6") (pin "16") (pinfunction "GND_16") (pintype "passive"))
      (node (ref "X6") (pin "17") (pinfunction "P1.7_17") (pintype "passive"))
      (node (ref "X6") (pin "19") (pinfunction "GND_19") (pintype "passive"))
      (node (ref "X6") (pin "22") (pinfunction "GND_22") (pintype "passive"))
      (node (ref "X6") (pin "25") (pinfunction "GND_25") (pintype "passive"))
      (node (ref "X6") (pin "28") (pinfunction "GND_28") (pintype "passive"))
      (node (ref "X6") (pin "29") (pinfunction "P2.0_29") (pintype "passive"))
      (node (ref "X6") (pin "30") (pinfunction "P2.2_30") (pintype "passive"))
      (node (ref "X6") (pin "31") (pinfunction "GND_31") (pintype "passive"))
      (node (ref "X6") (pin "32") (pinfunction "P1.6_32") (pintype "passive"))
      (node (ref "X6") (pin "33") (pinfunction "P1.4_33") (pintype "passive"))
      (node (ref "X6") (pin "34") (pinfunction "GND_34") (pintype "passive"))
      (node (ref "X6") (pin "35") (pinfunction "P1.0_35") (pintype "passive"))
      (node (ref "X6") (pin "36") (pinfunction "P1.2_36") (pintype "passive"))
      (node (ref "X6") (pin "37") (pinfunction "GND_37") (pintype "passive"))
      (node (ref "X6") (pin "4") (pinfunction "GND_4") (pintype "passive"))
      (node (ref "X6") (pin "40") (pinfunction "GND_40") (pintype "passive"))
      (node (ref "X6") (pin "42") (pinfunction "P0.2_42") (pintype "passive"))
      (node (ref "X6") (pin "43") (pinfunction "GND_43") (pintype "passive"))
      (node (ref "X6") (pin "45") (pinfunction "GND_45") (pintype "passive"))
      (node (ref "X6") (pin "46") (pinfunction "GND_46") (pintype "passive"))
      (node (ref "X6") (pin "47") (pinfunction "GND_47") (pintype "passive"))
      (node (ref "X6") (pin "48") (pinfunction "GND_48") (pintype "passive"))
      (node (ref "X6") (pin "49") (pinfunction "GND_49") (pintype "passive"))
      (node (ref "X6") (pin "50") (pinfunction "GND_50") (pintype "passive"))
      (node (ref "X6") (pin "6") (pinfunction "P0.1_6") (pintype "passive"))
      (node (ref "X6") (pin "7") (pinfunction "GND_7") (pintype "passive"))
      (node (ref "X6") (pin "8") (pinfunction "P0.3_8") (pintype "passive"))
      (node (ref "X6") (pin "9") (pinfunction "P0.5_9") (pintype "passive"))
    )
    (net (code "62") (name "unconnected-(D2-RIN3_N-Pad5)") (class "Default")
      (node (ref "D2") (pin "5") (pinfunction "RIN3_N_5") (pintype "passive"))
    )
    (net (code "63") (name "unconnected-(D2-RIN3_P-Pad6)") (class "Default")
      (node (ref "D2") (pin "6") (pinfunction "RIN3_P_6") (pintype "passive"))
    )
    (net (code "64") (name "unconnected-(D2-ROUT3-Pad11)") (class "Default")
      (node (ref "D2") (pin "11") (pinfunction "ROUT3_11") (pintype "passive"))
    )
    (net (code "65") (name "unconnected-(D3-RIN3_N-Pad5)") (class "Default")
      (node (ref "D3") (pin "5") (pinfunction "RIN3_N_5") (pintype "passive"))
    )
    (net (code "66") (name "unconnected-(D3-RIN3_P-Pad6)") (class "Default")
      (node (ref "D3") (pin "6") (pinfunction "RIN3_P_6") (pintype "passive"))
    )
    (net (code "67") (name "unconnected-(D3-ROUT3-Pad11)") (class "Default")
      (node (ref "D3") (pin "11") (pinfunction "ROUT3_11") (pintype "passive"))
    )
    (net (code "68") (name "unconnected-(X5-2-Pad3)") (class "Default")
      (node (ref "X5") (pin "3") (pinfunction "2_3") (pintype "passive"))
    )
    (net (code "69") (name "unconnected-(X6-CLKOUT-Pad3)") (class "Default")
      (node (ref "X6") (pin "3") (pinfunction "CLKOUT_3") (pintype "passive"))
    )
    (net (code "70") (name "unconnected-(X6-GCLK0-Pad2)") (class "Default")
      (node (ref "X6") (pin "2") (pinfunction "GCLK0_2") (pintype "passive"))
    )
  )
)
